# nixie-tube-clock_mainboard.net
KiCad netlist of a schematic drawn in EAGLE
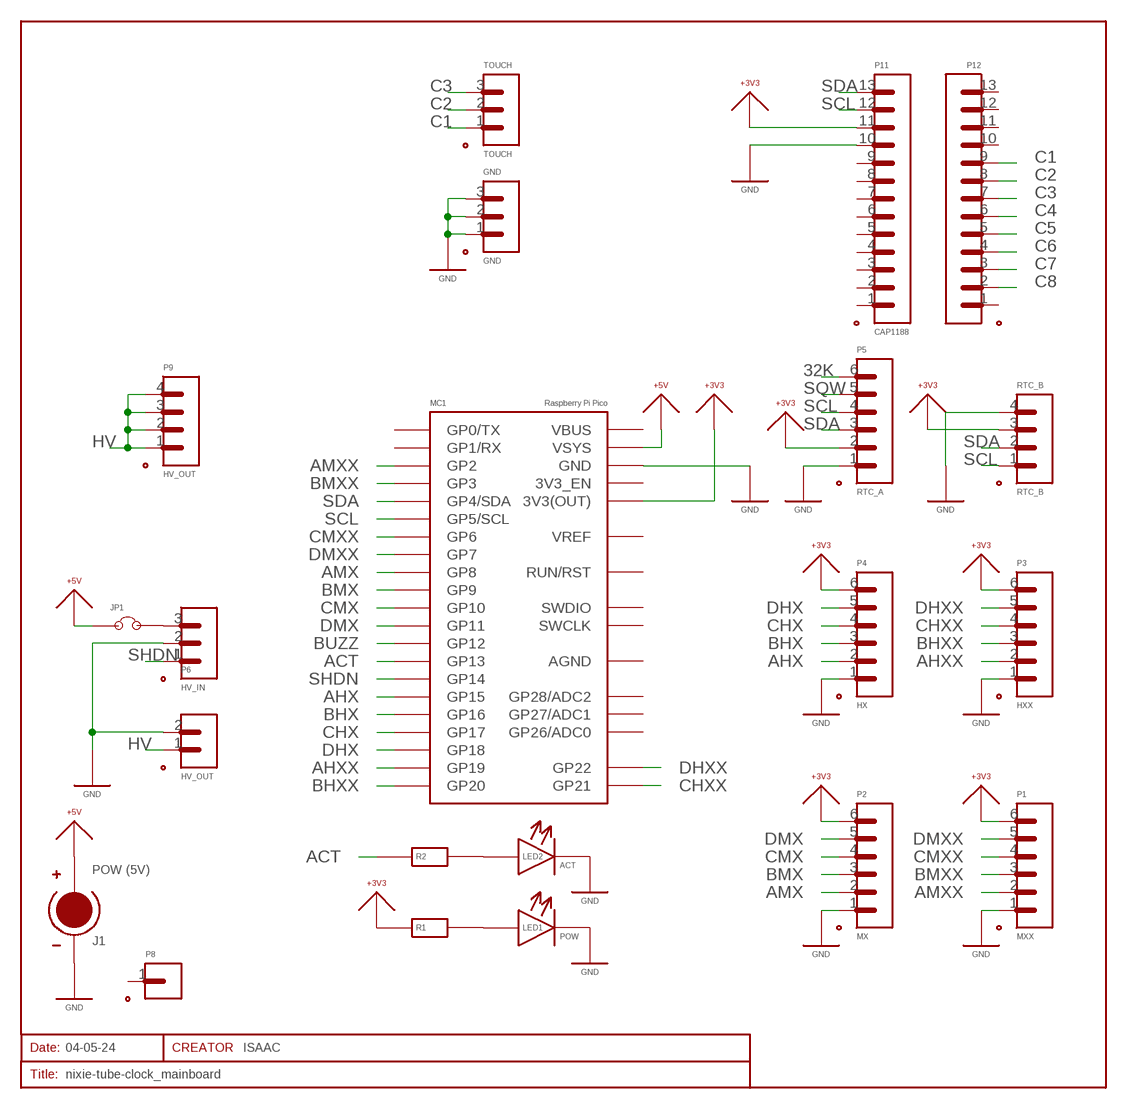
[diagram p0: schematic, sheet 1]

(export (version "E")
  (design (tool "Eeschema 10.0.6"))
  (components
    (comp (ref "CREATOR")
      (value "ISAAC")
      (footprint "eagle-import:INFO_T")
      (libsource (lib "eagle-import") (part "INFO_T"))
    )
    (comp (ref "GND")
      (value "GND")
      (footprint "eagle-import:XH2.54_3-PIN")
      (libsource (lib "eagle-import") (part "PORT_3-PIN_XH2.54"))
    )
    (comp (ref "J1")
      (value "POW (5V)")
      (footprint "eagle-import:XH2.54_2-PIN")
      (libsource (lib "eagle-import") (part "DC_POWER_CENTER-POS_XH2.54"))
    )
    (comp (ref "JP1")
      (value "JUMPER_2-WAY_HEADER")
      (footprint "eagle-import:HEADER_2-PIN_JUMPER")
      (libsource (lib "eagle-import") (part "JUMPER_2-WAY_HEADER"))
    )
    (comp (ref "LED1")
      (value "POW")
      (footprint "eagle-import:LED_3MM")
      (libsource (lib "eagle-import") (part "LED_3MM"))
    )
    (comp (ref "LED2")
      (value "ACT")
      (footprint "eagle-import:LED_3MM")
      (libsource (lib "eagle-import") (part "LED_3MM"))
    )
    (comp (ref "MC1")
      (value "RASPBERRY-PI-PICO_THT")
      (footprint "eagle-import:RASPBERRY-PI-PICO_THT")
      (libsource (lib "eagle-import") (part "RASPBERRY-PI-PICO_THT"))
    )
    (comp (ref "P1")
      (value "MXX")
      (footprint "eagle-import:XH2.54_6-PIN")
      (libsource (lib "eagle-import") (part "PORT_6-PIN_XH2.54"))
    )
    (comp (ref "P2")
      (value "MX")
      (footprint "eagle-import:XH2.54_6-PIN")
      (libsource (lib "eagle-import") (part "PORT_6-PIN_XH2.54"))
    )
    (comp (ref "P3")
      (value "HXX")
      (footprint "eagle-import:XH2.54_6-PIN")
      (libsource (lib "eagle-import") (part "PORT_6-PIN_XH2.54"))
    )
    (comp (ref "P4")
      (value "HX")
      (footprint "eagle-import:XH2.54_6-PIN")
      (libsource (lib "eagle-import") (part "PORT_6-PIN_XH2.54"))
    )
    (comp (ref "P5")
      (value "RTC_A")
      (footprint "eagle-import:HEADER_6-PIN")
      (libsource (lib "eagle-import") (part "PORT_6-PIN_HEADER"))
    )
    (comp (ref "P6")
      (value "HV_OUT")
      (footprint "eagle-import:HEADER_2-PIN")
      (libsource (lib "eagle-import") (part "PORT_2-PIN_HEADER"))
    )
    (comp (ref "P7")
      (value "HV_IN")
      (footprint "eagle-import:HEADER_3-PIN")
      (libsource (lib "eagle-import") (part "PORT_3-PIN_HEADER"))
    )
    (comp (ref "P8")
      (value "PORT_1-PIN_HEADER")
      (footprint "eagle-import:HEADER_1-PIN")
      (libsource (lib "eagle-import") (part "PORT_1-PIN_HEADER"))
    )
    (comp (ref "P9")
      (value "HV_OUT")
      (footprint "eagle-import:XH2.54_4-PIN")
      (libsource (lib "eagle-import") (part "PORT_4-PIN_XH2.54"))
    )
    (comp (ref "P11")
      (value "CAP1188")
      (footprint "eagle-import:HEADER_13-PIN")
      (libsource (lib "eagle-import") (part "PORT_13-PIN_HEADER"))
    )
    (comp (ref "P12")
      (value "PORT_13-PIN_HEADER")
      (footprint "eagle-import:HEADER_13-PIN")
      (libsource (lib "eagle-import") (part "PORT_13-PIN_HEADER"))
    )
    (comp (ref "R1")
      (value "RESISTOR")
      (footprint "eagle-import:RESISTOR_10.16MM")
      (libsource (lib "eagle-import") (part "RESISTOR"))
    )
    (comp (ref "R2")
      (value "RESISTOR")
      (footprint "eagle-import:RESISTOR_10.16MM")
      (libsource (lib "eagle-import") (part "RESISTOR"))
    )
    (comp (ref "RTC_B")
      (value "RTC_B")
      (footprint "eagle-import:XH2.54_4-PIN")
      (libsource (lib "eagle-import") (part "PORT_4-PIN_XH2.54"))
    )
    (comp (ref "SCHEMATIC1")
      (value "04-05-24")
      (footprint "eagle-import:SHEET")
      (libsource (lib "eagle-import") (part "SHEET"))
    )
    (comp (ref "TOUCH")
      (value "TOUCH")
      (footprint "eagle-import:XH2.54_3-PIN")
      (libsource (lib "eagle-import") (part "PORT_3-PIN_XH2.54"))
    )
  )
  (nets
    (net (code "1") (name "+3V3") (class "Default")
      (node (ref "MC1") (pin "36") (pinfunction "3V3(OUT)_36") (pintype "power_in"))
      (node (ref "P1") (pin "6") (pinfunction "6_6") (pintype "bidirectional"))
      (node (ref "P11") (pin "11") (pinfunction "11_11") (pintype "bidirectional"))
      (node (ref "P2") (pin "6") (pinfunction "6_6") (pintype "bidirectional"))
      (node (ref "P3") (pin "6") (pinfunction "6_6") (pintype "bidirectional"))
      (node (ref "P4") (pin "6") (pinfunction "6_6") (pintype "bidirectional"))
      (node (ref "P5") (pin "2") (pinfunction "2_2") (pintype "bidirectional"))
      (node (ref "R1") (pin "1") (pinfunction "1_1") (pintype "bidirectional"))
      (node (ref "RTC_B") (pin "3") (pinfunction "3_3") (pintype "bidirectional"))
    )
    (net (code "2") (name "+5V") (class "Default")
      (node (ref "J1") (pin "2") (pinfunction "+_2") (pintype "output"))
      (node (ref "JP1") (pin "1") (pinfunction "1_1") (pintype "bidirectional"))
      (node (ref "MC1") (pin "39") (pinfunction "VSYS_39") (pintype "bidirectional"))
    )
    (net (code "3") (name "/32K") (class "Default")
      (node (ref "P5") (pin "6") (pinfunction "6_6") (pintype "bidirectional"))
    )
    (net (code "4") (name "/ACT") (class "Default")
      (node (ref "MC1") (pin "17") (pinfunction "GP13_17") (pintype "bidirectional"))
      (node (ref "R2") (pin "1") (pinfunction "1_1") (pintype "bidirectional"))
    )
    (net (code "5") (name "/AGND") (class "Default")
      (node (ref "MC1") (pin "33") (pinfunction "AGND_33") (pintype "power_in"))
    )
    (net (code "6") (name "/AHX") (class "Default")
      (node (ref "MC1") (pin "20") (pinfunction "GP15_20") (pintype "bidirectional"))
      (node (ref "P4") (pin "2") (pinfunction "2_2") (pintype "bidirectional"))
    )
    (net (code "7") (name "/AHXX") (class "Default")
      (node (ref "MC1") (pin "25") (pinfunction "GP19_25") (pintype "bidirectional"))
      (node (ref "P3") (pin "2") (pinfunction "2_2") (pintype "bidirectional"))
    )
    (net (code "8") (name "/AMX") (class "Default")
      (node (ref "MC1") (pin "11") (pinfunction "GP8_11") (pintype "bidirectional"))
      (node (ref "P2") (pin "2") (pinfunction "2_2") (pintype "bidirectional"))
    )
    (net (code "9") (name "/AMXX") (class "Default")
      (node (ref "MC1") (pin "4") (pinfunction "GP2_4") (pintype "bidirectional"))
      (node (ref "P1") (pin "2") (pinfunction "2_2") (pintype "bidirectional"))
    )
    (net (code "10") (name "/BHX") (class "Default")
      (node (ref "MC1") (pin "21") (pinfunction "GP16_21") (pintype "bidirectional"))
      (node (ref "P4") (pin "3") (pinfunction "3_3") (pintype "bidirectional"))
    )
    (net (code "11") (name "/BHXX") (class "Default")
      (node (ref "MC1") (pin "26") (pinfunction "GP20_26") (pintype "bidirectional"))
      (node (ref "P3") (pin "3") (pinfunction "3_3") (pintype "bidirectional"))
    )
    (net (code "12") (name "/BMX") (class "Default")
      (node (ref "MC1") (pin "12") (pinfunction "GP9_12") (pintype "bidirectional"))
      (node (ref "P2") (pin "3") (pinfunction "3_3") (pintype "bidirectional"))
    )
    (net (code "13") (name "/BMXX") (class "Default")
      (node (ref "MC1") (pin "5") (pinfunction "GP3_5") (pintype "bidirectional"))
      (node (ref "P1") (pin "3") (pinfunction "3_3") (pintype "bidirectional"))
    )
    (net (code "14") (name "/BUZZ") (class "Default")
      (node (ref "MC1") (pin "16") (pinfunction "GP12_16") (pintype "bidirectional"))
    )
    (net (code "15") (name "/C1") (class "Default")
      (node (ref "P12") (pin "9") (pinfunction "9_9") (pintype "bidirectional"))
      (node (ref "TOUCH") (pin "1") (pinfunction "1_1") (pintype "bidirectional"))
    )
    (net (code "16") (name "/C2") (class "Default")
      (node (ref "P12") (pin "8") (pinfunction "8_8") (pintype "bidirectional"))
      (node (ref "TOUCH") (pin "2") (pinfunction "2_2") (pintype "bidirectional"))
    )
    (net (code "17") (name "/C3") (class "Default")
      (node (ref "P12") (pin "7") (pinfunction "7_7") (pintype "bidirectional"))
      (node (ref "TOUCH") (pin "3") (pinfunction "3_3") (pintype "bidirectional"))
    )
    (net (code "18") (name "/C4") (class "Default")
      (node (ref "P12") (pin "6") (pinfunction "6_6") (pintype "bidirectional"))
    )
    (net (code "19") (name "/C5") (class "Default")
      (node (ref "P12") (pin "5") (pinfunction "5_5") (pintype "bidirectional"))
    )
    (net (code "20") (name "/C6") (class "Default")
      (node (ref "P12") (pin "4") (pinfunction "4_4") (pintype "bidirectional"))
    )
    (net (code "21") (name "/C7") (class "Default")
      (node (ref "P12") (pin "3") (pinfunction "3_3") (pintype "bidirectional"))
    )
    (net (code "22") (name "/C8") (class "Default")
      (node (ref "P12") (pin "2") (pinfunction "2_2") (pintype "bidirectional"))
    )
    (net (code "23") (name "/CHX") (class "Default")
      (node (ref "MC1") (pin "22") (pinfunction "GP17_22") (pintype "bidirectional"))
      (node (ref "P4") (pin "4") (pinfunction "4_4") (pintype "bidirectional"))
    )
    (net (code "24") (name "/CHXX") (class "Default")
      (node (ref "MC1") (pin "27") (pinfunction "GP21_27") (pintype "bidirectional"))
      (node (ref "P3") (pin "4") (pinfunction "4_4") (pintype "bidirectional"))
    )
    (net (code "25") (name "/CMX") (class "Default")
      (node (ref "MC1") (pin "14") (pinfunction "GP10_14") (pintype "bidirectional"))
      (node (ref "P2") (pin "4") (pinfunction "4_4") (pintype "bidirectional"))
    )
    (net (code "26") (name "/CMXX") (class "Default")
      (node (ref "MC1") (pin "9") (pinfunction "GP6_9") (pintype "bidirectional"))
      (node (ref "P1") (pin "4") (pinfunction "4_4") (pintype "bidirectional"))
    )
    (net (code "27") (name "/DHX") (class "Default")
      (node (ref "MC1") (pin "24") (pinfunction "GP18_24") (pintype "bidirectional"))
      (node (ref "P4") (pin "5") (pinfunction "5_5") (pintype "bidirectional"))
    )
    (net (code "28") (name "/DHXX") (class "Default")
      (node (ref "MC1") (pin "29") (pinfunction "GP22_29") (pintype "bidirectional"))
      (node (ref "P3") (pin "5") (pinfunction "5_5") (pintype "bidirectional"))
    )
    (net (code "29") (name "/DMX") (class "Default")
      (node (ref "MC1") (pin "15") (pinfunction "GP11_15") (pintype "bidirectional"))
      (node (ref "P2") (pin "5") (pinfunction "5_5") (pintype "bidirectional"))
    )
    (net (code "30") (name "/DMXX") (class "Default")
      (node (ref "MC1") (pin "10") (pinfunction "GP7_10") (pintype "bidirectional"))
      (node (ref "P1") (pin "5") (pinfunction "5_5") (pintype "bidirectional"))
    )
    (net (code "31") (name "/HV") (class "Default")
      (node (ref "P6") (pin "1") (pinfunction "1_1") (pintype "bidirectional"))
      (node (ref "P9") (pin "1") (pinfunction "1_1") (pintype "bidirectional"))
      (node (ref "P9") (pin "2") (pinfunction "2_2") (pintype "bidirectional"))
      (node (ref "P9") (pin "3") (pinfunction "3_3") (pintype "bidirectional"))
      (node (ref "P9") (pin "4") (pinfunction "4_4") (pintype "bidirectional"))
    )
    (net (code "32") (name "/SCL") (class "Default")
      (node (ref "MC1") (pin "7") (pinfunction "GP5/SCL_7") (pintype "bidirectional"))
      (node (ref "P11") (pin "12") (pinfunction "12_12") (pintype "bidirectional"))
      (node (ref "P5") (pin "4") (pinfunction "4_4") (pintype "bidirectional"))
      (node (ref "RTC_B") (pin "1") (pinfunction "1_1") (pintype "bidirectional"))
    )
    (net (code "33") (name "/SDA") (class "Default")
      (node (ref "MC1") (pin "6") (pinfunction "GP4/SDA_6") (pintype "bidirectional"))
      (node (ref "P11") (pin "13") (pinfunction "13_13") (pintype "bidirectional"))
      (node (ref "P5") (pin "3") (pinfunction "3_3") (pintype "bidirectional"))
      (node (ref "RTC_B") (pin "2") (pinfunction "2_2") (pintype "bidirectional"))
    )
    (net (code "34") (name "/SHDN") (class "Default")
      (node (ref "MC1") (pin "19") (pinfunction "GP14_19") (pintype "bidirectional"))
      (node (ref "P7") (pin "1") (pinfunction "1_1") (pintype "bidirectional"))
    )
    (net (code "35") (name "/SQW") (class "Default")
      (node (ref "P5") (pin "5") (pinfunction "5_5") (pintype "bidirectional"))
    )
    (net (code "36") (name "GND") (class "Default")
      (node (ref "GND") (pin "1") (pinfunction "1_1") (pintype "bidirectional"))
      (node (ref "GND") (pin "2") (pinfunction "2_2") (pintype "bidirectional"))
      (node (ref "GND") (pin "3") (pinfunction "3_3") (pintype "bidirectional"))
      (node (ref "J1") (pin "1") (pinfunction "GND_1") (pintype "power_in"))
      (node (ref "LED1") (pin "-") (pinfunction "-_-") (pintype "output"))
      (node (ref "LED2") (pin "-") (pinfunction "-_-") (pintype "output"))
      (node (ref "MC1") (pin "13") (pinfunction "GND_13") (pintype "power_in"))
      (node (ref "MC1") (pin "18") (pinfunction "GND_18") (pintype "power_in"))
      (node (ref "MC1") (pin "23") (pinfunction "GND_23") (pintype "power_in"))
      (node (ref "MC1") (pin "28") (pinfunction "GND_28") (pintype "power_in"))
      (node (ref "MC1") (pin "3") (pinfunction "GND_3") (pintype "power_in"))
      (node (ref "MC1") (pin "38") (pinfunction "GND_38") (pintype "power_in"))
      (node (ref "MC1") (pin "8") (pinfunction "GND_8") (pintype "power_in"))
      (node (ref "MC1") (pin "D_GND") (pinfunction "GND_D_GND") (pintype "power_in"))
      (node (ref "P1") (pin "1") (pinfunction "1_1") (pintype "bidirectional"))
      (node (ref "P11") (pin "10") (pinfunction "10_10") (pintype "bidirectional"))
      (node (ref "P2") (pin "1") (pinfunction "1_1") (pintype "bidirectional"))
      (node (ref "P3") (pin "1") (pinfunction "1_1") (pintype "bidirectional"))
      (node (ref "P4") (pin "1") (pinfunction "1_1") (pintype "bidirectional"))
      (node (ref "P5") (pin "1") (pinfunction "1_1") (pintype "bidirectional"))
      (node (ref "P6") (pin "2") (pinfunction "2_2") (pintype "bidirectional"))
      (node (ref "P7") (pin "2") (pinfunction "2_2") (pintype "bidirectional"))
      (node (ref "RTC_B") (pin "4") (pinfunction "4_4") (pintype "bidirectional"))
    )
    (net (code "37") (name "Net-(JP1-Pad2)") (class "Default")
      (node (ref "JP1") (pin "2") (pinfunction "2_2") (pintype "bidirectional"))
      (node (ref "P7") (pin "3") (pinfunction "3_3") (pintype "bidirectional"))
    )
    (net (code "38") (name "Net-(LED1-Pad+)") (class "Default")
      (node (ref "LED1") (pin "+") (pinfunction "+_+") (pintype "input"))
      (node (ref "R1") (pin "2") (pinfunction "2_2") (pintype "bidirectional"))
    )
    (net (code "39") (name "Net-(LED2-Pad+)") (class "Default")
      (node (ref "LED2") (pin "+") (pinfunction "+_+") (pintype "input"))
      (node (ref "R2") (pin "2") (pinfunction "2_2") (pintype "bidirectional"))
    )
    (net (code "40") (name "unconnected-(MC1-3V3_EN-Pad37)") (class "Default")
      (node (ref "MC1") (pin "37") (pinfunction "3V3_EN_37") (pintype "bidirectional"))
    )
    (net (code "41") (name "unconnected-(MC1-GP0{slash}TX-Pad1)") (class "Default")
      (node (ref "MC1") (pin "1") (pinfunction "GP0/TX_1") (pintype "bidirectional"))
    )
    (net (code "42") (name "unconnected-(MC1-GP1{slash}RX-Pad2)") (class "Default")
      (node (ref "MC1") (pin "2") (pinfunction "GP1/RX_2") (pintype "bidirectional"))
    )
    (net (code "43") (name "unconnected-(MC1-GP26{slash}ADC0-Pad31)") (class "Default")
      (node (ref "MC1") (pin "31") (pinfunction "GP26/ADC0_31") (pintype "bidirectional"))
    )
    (net (code "44") (name "unconnected-(MC1-GP27{slash}ADC1-Pad32)") (class "Default")
      (node (ref "MC1") (pin "32") (pinfunction "GP27/ADC1_32") (pintype "bidirectional"))
    )
    (net (code "45") (name "unconnected-(MC1-GP28{slash}ADC2-Pad34)") (class "Default")
      (node (ref "MC1") (pin "34") (pinfunction "GP28/ADC2_34") (pintype "bidirectional"))
    )
    (net (code "46") (name "unconnected-(MC1-PadSWCLK)") (class "Default")
      (node (ref "MC1") (pin "SWCLK") (pinfunction "SWCLK_SWCLK") (pintype "bidirectional"))
    )
    (net (code "47") (name "unconnected-(MC1-PadSWDIO)") (class "Default")
      (node (ref "MC1") (pin "SWDIO") (pinfunction "SWDIO_SWDIO") (pintype "bidirectional"))
    )
    (net (code "48") (name "unconnected-(MC1-RUN{slash}RST-Pad30)") (class "Default")
      (node (ref "MC1") (pin "30") (pinfunction "RUN/RST_30") (pintype "bidirectional"))
    )
    (net (code "49") (name "unconnected-(MC1-VBUS-Pad40)") (class "Default")
      (node (ref "MC1") (pin "40") (pinfunction "VBUS_40") (pintype "bidirectional"))
    )
    (net (code "50") (name "unconnected-(MC1-VREF-Pad35)") (class "Default")
      (node (ref "MC1") (pin "35") (pinfunction "VREF_35") (pintype "bidirectional"))
    )
    (net (code "51") (name "unconnected-(P8-Pad1)") (class "Default")
      (node (ref "P8") (pin "1") (pinfunction "1_1") (pintype "bidirectional"))
    )
    (net (code "52") (name "unconnected-(P11-Pad1)") (class "Default")
      (node (ref "P11") (pin "1") (pinfunction "1_1") (pintype "bidirectional"))
    )
    (net (code "53") (name "unconnected-(P11-Pad2)") (class "Default")
      (node (ref "P11") (pin "2") (pinfunction "2_2") (pintype "bidirectional"))
    )
    (net (code "54") (name "unconnected-(P11-Pad3)") (class "Default")
      (node (ref "P11") (pin "3") (pinfunction "3_3") (pintype "bidirectional"))
    )
    (net (code "55") (name "unconnected-(P11-Pad4)") (class "Default")
      (node (ref "P11") (pin "4") (pinfunction "4_4") (pintype "bidirectional"))
    )
    (net (code "56") (name "unconnected-(P11-Pad5)") (class "Default")
      (node (ref "P11") (pin "5") (pinfunction "5_5") (pintype "bidirectional"))
    )
    (net (code "57") (name "unconnected-(P11-Pad6)") (class "Default")
      (node (ref "P11") (pin "6") (pinfunction "6_6") (pintype "bidirectional"))
    )
    (net (code "58") (name "unconnected-(P11-Pad7)") (class "Default")
      (node (ref "P11") (pin "7") (pinfunction "7_7") (pintype "bidirectional"))
    )
    (net (code "59") (name "unconnected-(P11-Pad8)") (class "Default")
      (node (ref "P11") (pin "8") (pinfunction "8_8") (pintype "bidirectional"))
    )
    (net (code "60") (name "unconnected-(P11-Pad9)") (class "Default")
      (node (ref "P11") (pin "9") (pinfunction "9_9") (pintype "bidirectional"))
    )
    (net (code "61") (name "unconnected-(P12-Pad1)") (class "Default")
      (node (ref "P12") (pin "1") (pinfunction "1_1") (pintype "bidirectional"))
    )
    (net (code "62") (name "unconnected-(P12-Pad10)") (class "Default")
      (node (ref "P12") (pin "10") (pinfunction "10_10") (pintype "bidirectional"))
    )
    (net (code "63") (name "unconnected-(P12-Pad11)") (class "Default")
      (node (ref "P12") (pin "11") (pinfunction "11_11") (pintype "bidirectional"))
    )
    (net (code "64") (name "unconnected-(P12-Pad12)") (class "Default")
      (node (ref "P12") (pin "12") (pinfunction "12_12") (pintype "bidirectional"))
    )
    (net (code "65") (name "unconnected-(P12-Pad13)") (class "Default")
      (node (ref "P12") (pin "13") (pinfunction "13_13") (pintype "bidirectional"))
    )
  )
)
